# Connector_board.net
KiCad netlist of a schematic drawn in EAGLE
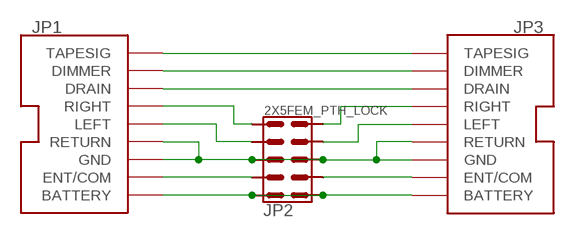
[diagram p0: schematic, sheet 1]

(export (version "E")
  (design (tool "Eeschema 10.0.6"))
  (components
    (comp (ref "JP1")
      (value "CASSETTEPLUG")
      (footprint "eagle-import:9WAYMICROPACK100")
      (libsource (lib "eagle-import") (part "CASSETTEPLUG"))
    )
    (comp (ref "JP2")
      (value "2X5FEM_PTH_LOCK")
      (footprint "eagle-import:2X5PTHFEMLOCK")
      (libsource (lib "eagle-import") (part "2X5FEM_PTH_LOCK"))
    )
    (comp (ref "JP3")
      (value "CASSETTEPLUGSTRAIGHT")
      (footprint "eagle-import:9PINCONNECTOR")
      (libsource (lib "eagle-import") (part "CASSETTEPLUGSTRAIGHT"))
    )
  )
  (nets
    (net (code "1") (name "Net-(JP1-GND-PadP$10)") (class "Default")
      (node (ref "JP1") (pin "GND") (pinfunction "GND_GND") (pintype "bidirectional"))
      (node (ref "JP1") (pin "P$10") (pinfunction "GND_P$10") (pintype "bidirectional"))
      (node (ref "JP1") (pin "P$11") (pinfunction "GND_P$11") (pintype "bidirectional"))
      (node (ref "JP1") (pin "RETURN") (pinfunction "RETURN_RETURN") (pintype "bidirectional"))
      (node (ref "JP2") (pin "P$3") (pinfunction "P$3_P$3") (pintype "bidirectional"))
      (node (ref "JP2") (pin "P$8") (pinfunction "P$8_P$8") (pintype "bidirectional"))
      (node (ref "JP3") (pin "GND") (pinfunction "GND_GND") (pintype "bidirectional"))
      (node (ref "JP3") (pin "RETURN") (pinfunction "RETURN_RETURN") (pintype "bidirectional"))
    )
    (net (code "2") (name "Net-(JP1-PadBATTERY)") (class "Default")
      (node (ref "JP1") (pin "BATTERY") (pinfunction "BATTERY_BATTERY") (pintype "bidirectional"))
      (node (ref "JP2") (pin "P$1") (pinfunction "P$1_P$1") (pintype "bidirectional"))
      (node (ref "JP2") (pin "P$10") (pinfunction "P$10_P$10") (pintype "bidirectional"))
      (node (ref "JP3") (pin "BATTERY") (pinfunction "BATTERY_BATTERY") (pintype "bidirectional"))
    )
    (net (code "3") (name "Net-(JP1-PadDIMMER)") (class "Default")
      (node (ref "JP1") (pin "DIMMER") (pinfunction "DIMMER_DIMMER") (pintype "bidirectional"))
      (node (ref "JP3") (pin "DIMMER") (pinfunction "DIMMER_DIMMER") (pintype "bidirectional"))
    )
    (net (code "4") (name "Net-(JP1-PadDRAIN)") (class "Default")
      (node (ref "JP1") (pin "DRAIN") (pinfunction "DRAIN_DRAIN") (pintype "bidirectional"))
      (node (ref "JP3") (pin "DRAIN") (pinfunction "DRAIN_DRAIN") (pintype "bidirectional"))
    )
    (net (code "5") (name "Net-(JP1-PadENT{slash}COM)") (class "Default")
      (node (ref "JP1") (pin "ENT/COM") (pinfunction "ENT/COM_ENT/COM") (pintype "bidirectional"))
      (node (ref "JP2") (pin "P$2") (pinfunction "P$2_P$2") (pintype "bidirectional"))
    )
    (net (code "6") (name "Net-(JP1-PadLEFT)") (class "Default")
      (node (ref "JP1") (pin "LEFT") (pinfunction "LEFT_LEFT") (pintype "bidirectional"))
      (node (ref "JP2") (pin "P$4") (pinfunction "P$4_P$4") (pintype "bidirectional"))
    )
    (net (code "7") (name "Net-(JP1-PadRIGHT)") (class "Default")
      (node (ref "JP1") (pin "RIGHT") (pinfunction "RIGHT_RIGHT") (pintype "bidirectional"))
      (node (ref "JP2") (pin "P$5") (pinfunction "P$5_P$5") (pintype "bidirectional"))
    )
    (net (code "8") (name "Net-(JP1-PadTAPESIG)") (class "Default")
      (node (ref "JP1") (pin "TAPESIG") (pinfunction "TAPESIG_TAPESIG") (pintype "bidirectional"))
      (node (ref "JP3") (pin "TAPESIG") (pinfunction "TAPESIG_TAPESIG") (pintype "bidirectional"))
    )
    (net (code "9") (name "Net-(JP2-PadP$6)") (class "Default")
      (node (ref "JP2") (pin "P$6") (pinfunction "P$6_P$6") (pintype "bidirectional"))
      (node (ref "JP3") (pin "RIGHT") (pinfunction "RIGHT_RIGHT") (pintype "bidirectional"))
    )
    (net (code "10") (name "Net-(JP2-PadP$7)") (class "Default")
      (node (ref "JP2") (pin "P$7") (pinfunction "P$7_P$7") (pintype "bidirectional"))
      (node (ref "JP3") (pin "LEFT") (pinfunction "LEFT_LEFT") (pintype "bidirectional"))
    )
    (net (code "11") (name "Net-(JP2-PadP$9)") (class "Default")
      (node (ref "JP2") (pin "P$9") (pinfunction "P$9_P$9") (pintype "bidirectional"))
      (node (ref "JP3") (pin "ENT/COM") (pinfunction "ENT/COM_ENT/COM") (pintype "bidirectional"))
    )
  )
)
